# BIT_0.net
KiCad netlist of a schematic drawn in EasyEDA
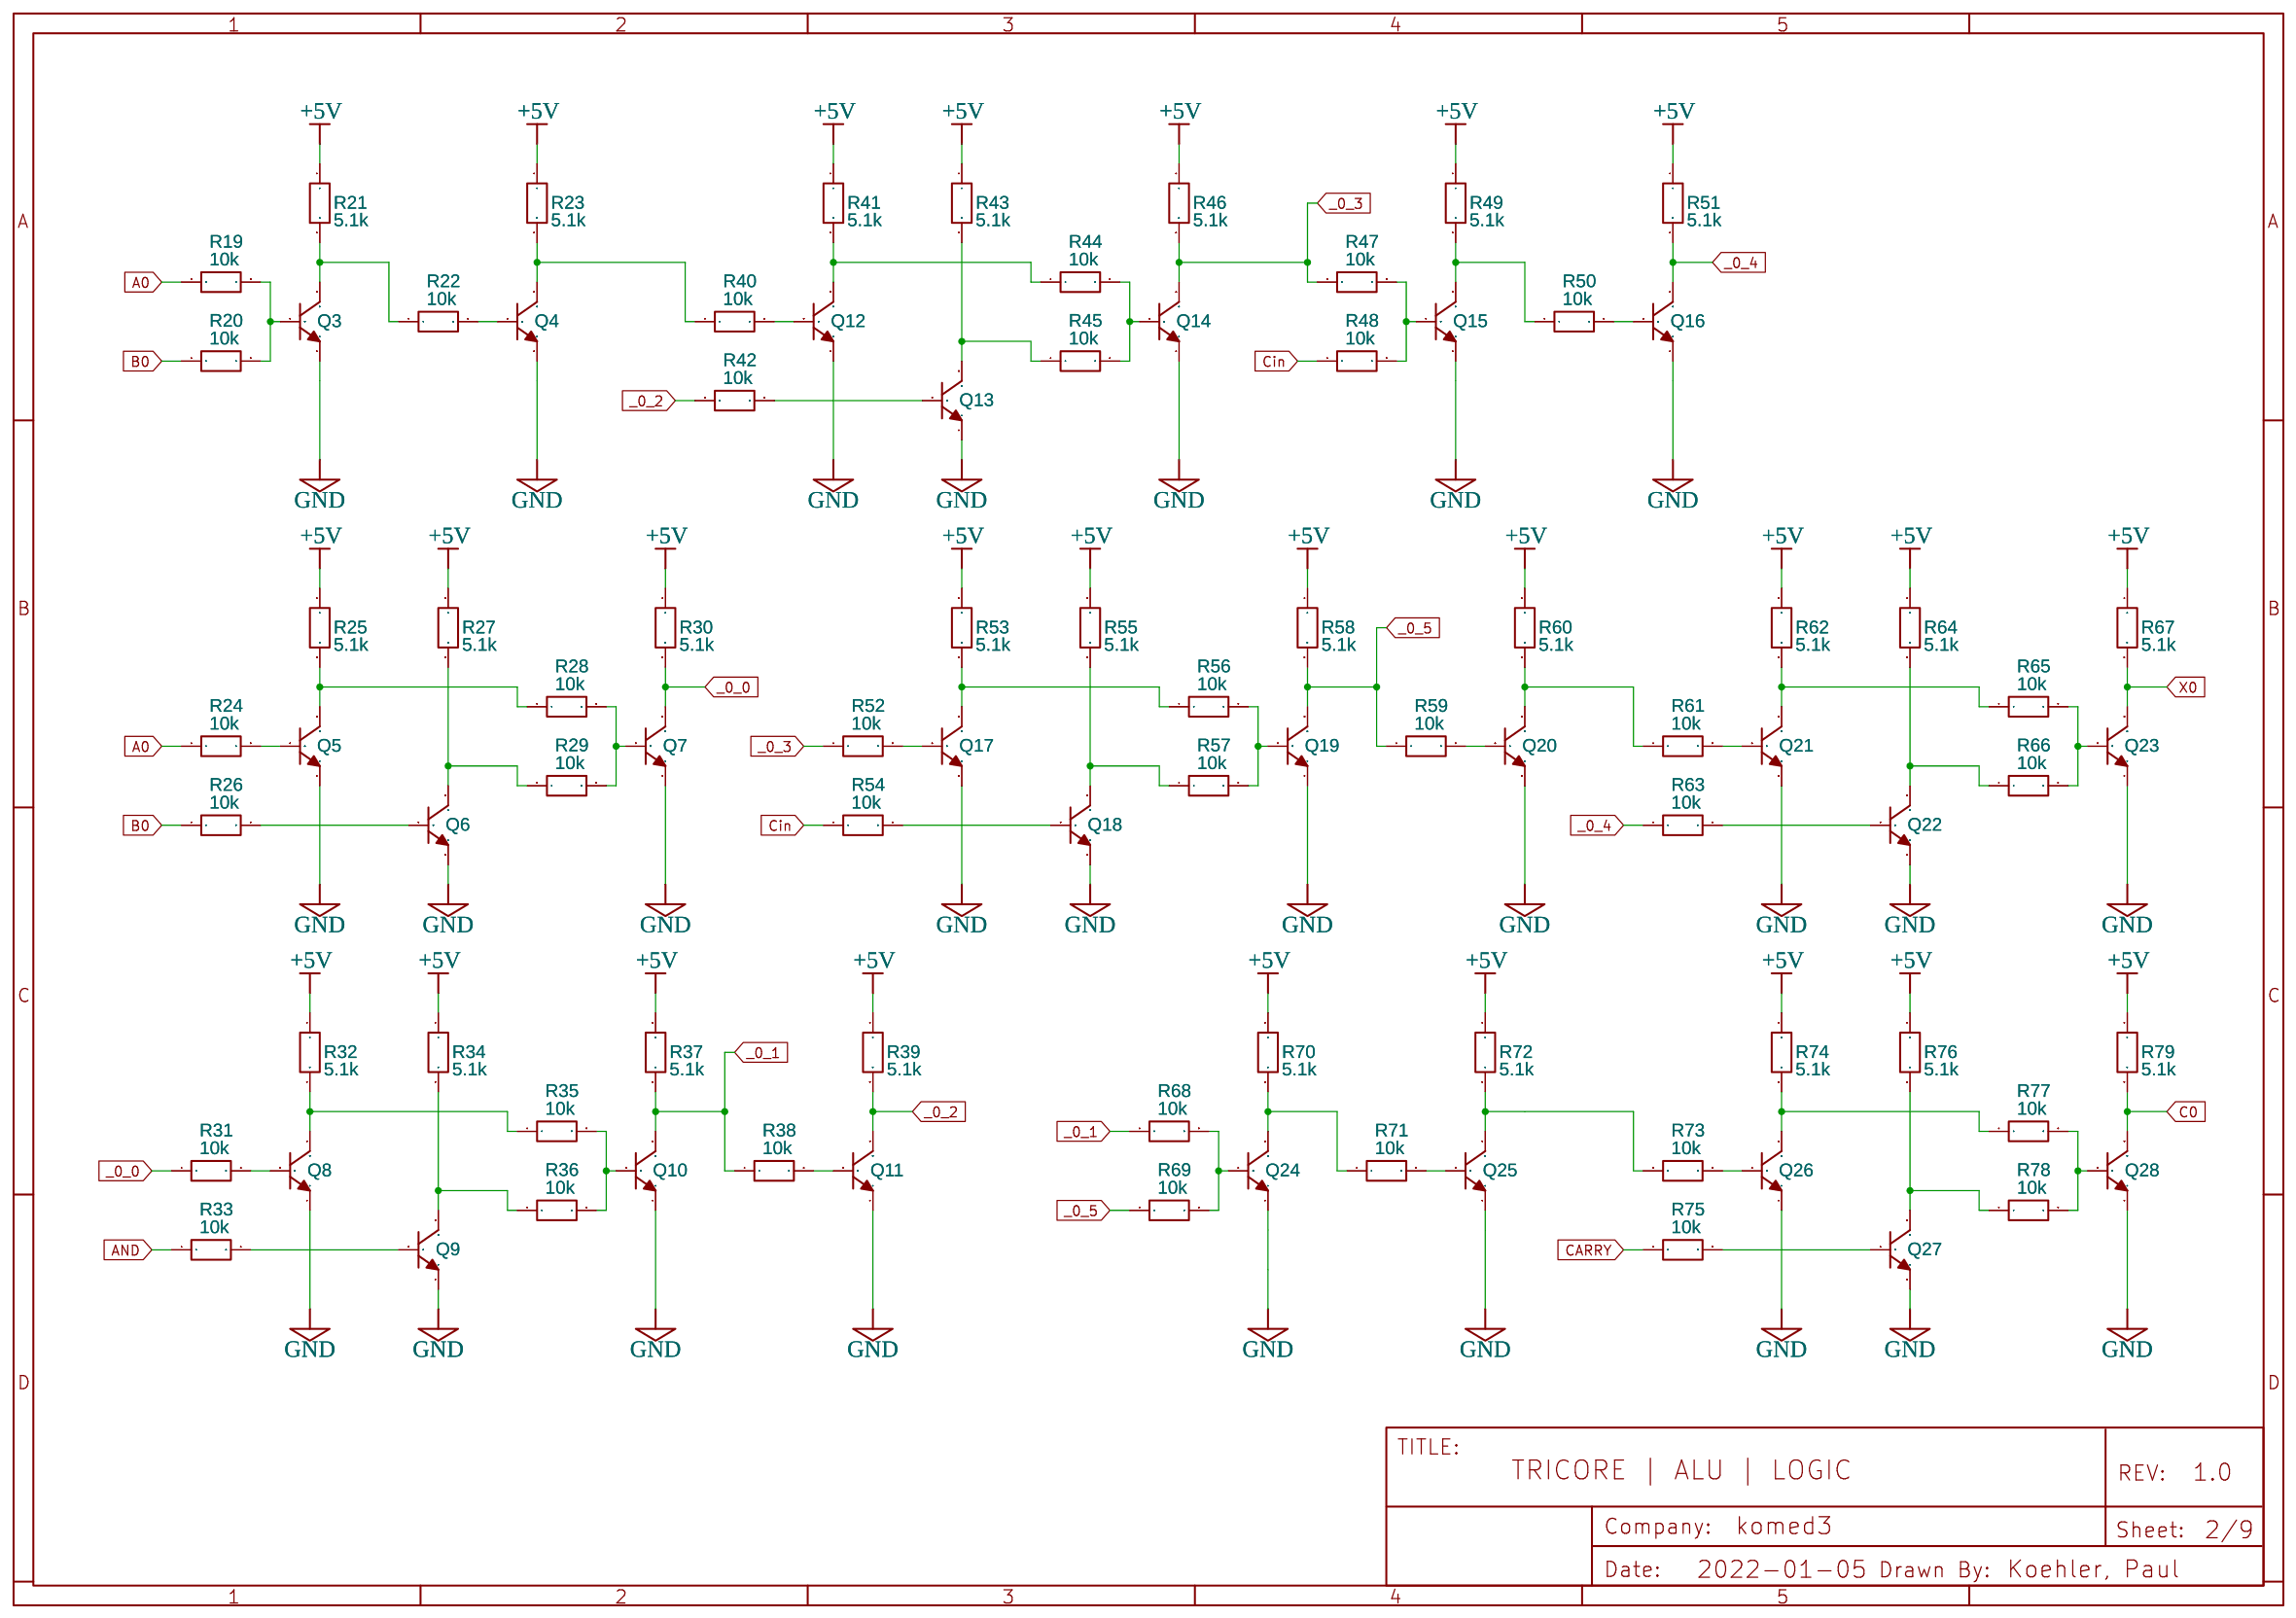
[diagram p0: schematic sheet]

(export (version "E")
  (design (tool "Eeschema 10.0.6"))
  (components
    (comp (ref "Q3")
      (value "2N3904(TO-92)")
      (fields (field (name "BOM_Manufacturer Part") "2N3904") (field (name "BOM_Supplier Part") "C118538"))
      (libsource (lib "") (part "2N3904(TO-92)"))
    )
    (comp (ref "Q4")
      (value "2N3904(TO-92)")
      (fields (field (name "BOM_Manufacturer Part") "2N3904") (field (name "BOM_Supplier Part") "C118538"))
      (libsource (lib "") (part "2N3904(TO-92)"))
    )
    (comp (ref "Q5")
      (value "2N3904(TO-92)")
      (fields (field (name "BOM_Manufacturer Part") "2N3904") (field (name "BOM_Supplier Part") "C118538"))
      (libsource (lib "") (part "2N3904(TO-92)"))
    )
    (comp (ref "Q6")
      (value "2N3904(TO-92)")
      (fields (field (name "BOM_Manufacturer Part") "2N3904") (field (name "BOM_Supplier Part") "C118538"))
      (libsource (lib "") (part "2N3904(TO-92)"))
    )
    (comp (ref "Q7")
      (value "2N3904(TO-92)")
      (fields (field (name "BOM_Manufacturer Part") "2N3904") (field (name "BOM_Supplier Part") "C118538"))
      (libsource (lib "") (part "2N3904(TO-92)"))
    )
    (comp (ref "Q8")
      (value "2N3904(TO-92)")
      (fields (field (name "BOM_Manufacturer Part") "2N3904") (field (name "BOM_Supplier Part") "C118538"))
      (libsource (lib "") (part "2N3904(TO-92)"))
    )
    (comp (ref "Q9")
      (value "2N3904(TO-92)")
      (fields (field (name "BOM_Manufacturer Part") "2N3904") (field (name "BOM_Supplier Part") "C118538"))
      (libsource (lib "") (part "2N3904(TO-92)"))
    )
    (comp (ref "Q10")
      (value "2N3904(TO-92)")
      (fields (field (name "BOM_Manufacturer Part") "2N3904") (field (name "BOM_Supplier Part") "C118538"))
      (libsource (lib "") (part "2N3904(TO-92)"))
    )
    (comp (ref "Q11")
      (value "2N3904(TO-92)")
      (fields (field (name "BOM_Manufacturer Part") "2N3904") (field (name "BOM_Supplier Part") "C118538"))
      (libsource (lib "") (part "2N3904(TO-92)"))
    )
    (comp (ref "Q12")
      (value "2N3904(TO-92)")
      (fields (field (name "BOM_Manufacturer Part") "2N3904") (field (name "BOM_Supplier Part") "C118538"))
      (libsource (lib "") (part "2N3904(TO-92)"))
    )
    (comp (ref "Q13")
      (value "2N3904(TO-92)")
      (fields (field (name "BOM_Manufacturer Part") "2N3904") (field (name "BOM_Supplier Part") "C118538"))
      (libsource (lib "") (part "2N3904(TO-92)"))
    )
    (comp (ref "Q14")
      (value "2N3904(TO-92)")
      (fields (field (name "BOM_Manufacturer Part") "2N3904") (field (name "BOM_Supplier Part") "C118538"))
      (libsource (lib "") (part "2N3904(TO-92)"))
    )
    (comp (ref "Q15")
      (value "2N3904(TO-92)")
      (fields (field (name "BOM_Manufacturer Part") "2N3904") (field (name "BOM_Supplier Part") "C118538"))
      (libsource (lib "") (part "2N3904(TO-92)"))
    )
    (comp (ref "Q16")
      (value "2N3904(TO-92)")
      (fields (field (name "BOM_Manufacturer Part") "2N3904") (field (name "BOM_Supplier Part") "C118538"))
      (libsource (lib "") (part "2N3904(TO-92)"))
    )
    (comp (ref "Q17")
      (value "2N3904(TO-92)")
      (fields (field (name "BOM_Manufacturer Part") "2N3904") (field (name "BOM_Supplier Part") "C118538"))
      (libsource (lib "") (part "2N3904(TO-92)"))
    )
    (comp (ref "Q18")
      (value "2N3904(TO-92)")
      (fields (field (name "BOM_Manufacturer Part") "2N3904") (field (name "BOM_Supplier Part") "C118538"))
      (libsource (lib "") (part "2N3904(TO-92)"))
    )
    (comp (ref "Q19")
      (value "2N3904(TO-92)")
      (fields (field (name "BOM_Manufacturer Part") "2N3904") (field (name "BOM_Supplier Part") "C118538"))
      (libsource (lib "") (part "2N3904(TO-92)"))
    )
    (comp (ref "Q20")
      (value "2N3904(TO-92)")
      (fields (field (name "BOM_Manufacturer Part") "2N3904") (field (name "BOM_Supplier Part") "C118538"))
      (libsource (lib "") (part "2N3904(TO-92)"))
    )
    (comp (ref "Q21")
      (value "2N3904(TO-92)")
      (fields (field (name "BOM_Manufacturer Part") "2N3904") (field (name "BOM_Supplier Part") "C118538"))
      (libsource (lib "") (part "2N3904(TO-92)"))
    )
    (comp (ref "Q22")
      (value "2N3904(TO-92)")
      (fields (field (name "BOM_Manufacturer Part") "2N3904") (field (name "BOM_Supplier Part") "C118538"))
      (libsource (lib "") (part "2N3904(TO-92)"))
    )
    (comp (ref "Q23")
      (value "2N3904(TO-92)")
      (fields (field (name "BOM_Manufacturer Part") "2N3904") (field (name "BOM_Supplier Part") "C118538"))
      (libsource (lib "") (part "2N3904(TO-92)"))
    )
    (comp (ref "Q24")
      (value "2N3904(TO-92)")
      (fields (field (name "BOM_Manufacturer Part") "2N3904") (field (name "BOM_Supplier Part") "C118538"))
      (libsource (lib "") (part "2N3904(TO-92)"))
    )
    (comp (ref "Q25")
      (value "2N3904(TO-92)")
      (fields (field (name "BOM_Manufacturer Part") "2N3904") (field (name "BOM_Supplier Part") "C118538"))
      (libsource (lib "") (part "2N3904(TO-92)"))
    )
    (comp (ref "Q26")
      (value "2N3904(TO-92)")
      (fields (field (name "BOM_Manufacturer Part") "2N3904") (field (name "BOM_Supplier Part") "C118538"))
      (libsource (lib "") (part "2N3904(TO-92)"))
    )
    (comp (ref "Q27")
      (value "2N3904(TO-92)")
      (fields (field (name "BOM_Manufacturer Part") "2N3904") (field (name "BOM_Supplier Part") "C118538"))
      (libsource (lib "") (part "2N3904(TO-92)"))
    )
    (comp (ref "Q28")
      (value "2N3904(TO-92)")
      (fields (field (name "BOM_Manufacturer Part") "2N3904") (field (name "BOM_Supplier Part") "C118538"))
      (libsource (lib "") (part "2N3904(TO-92)"))
    )
    (comp (ref "R19") (value "10k") (libsource (lib "") (part "R_AXIAL-0.3_EU_1")))
    (comp (ref "R20") (value "10k") (libsource (lib "") (part "R_AXIAL-0.3_EU_1")))
    (comp (ref "R21") (value "5.1k") (libsource (lib "") (part "R_AXIAL-0.3_EU")))
    (comp (ref "R22") (value "10k") (libsource (lib "") (part "R_AXIAL-0.3_EU_1")))
    (comp (ref "R23") (value "5.1k") (libsource (lib "") (part "R_AXIAL-0.3_EU")))
    (comp (ref "R24") (value "10k") (libsource (lib "") (part "R_AXIAL-0.3_EU_1")))
    (comp (ref "R25") (value "5.1k") (libsource (lib "") (part "R_AXIAL-0.3_EU")))
    (comp (ref "R26") (value "10k") (libsource (lib "") (part "R_AXIAL-0.3_EU_1")))
    (comp (ref "R27") (value "5.1k") (libsource (lib "") (part "R_AXIAL-0.3_EU")))
    (comp (ref "R28") (value "10k") (libsource (lib "") (part "R_AXIAL-0.3_EU_1")))
    (comp (ref "R29") (value "10k") (libsource (lib "") (part "R_AXIAL-0.3_EU_1")))
    (comp (ref "R30") (value "5.1k") (libsource (lib "") (part "R_AXIAL-0.3_EU")))
    (comp (ref "R31") (value "10k") (libsource (lib "") (part "R_AXIAL-0.3_EU_1")))
    (comp (ref "R32") (value "5.1k") (libsource (lib "") (part "R_AXIAL-0.3_EU")))
    (comp (ref "R33") (value "10k") (libsource (lib "") (part "R_AXIAL-0.3_EU_1")))
    (comp (ref "R34") (value "5.1k") (libsource (lib "") (part "R_AXIAL-0.3_EU")))
    (comp (ref "R35") (value "10k") (libsource (lib "") (part "R_AXIAL-0.3_EU_1")))
    (comp (ref "R36") (value "10k") (libsource (lib "") (part "R_AXIAL-0.3_EU_1")))
    (comp (ref "R37") (value "5.1k") (libsource (lib "") (part "R_AXIAL-0.3_EU")))
    (comp (ref "R38") (value "10k") (libsource (lib "") (part "R_AXIAL-0.3_EU_1")))
    (comp (ref "R39") (value "5.1k") (libsource (lib "") (part "R_AXIAL-0.3_EU")))
    (comp (ref "R40") (value "10k") (libsource (lib "") (part "R_AXIAL-0.3_EU_1")))
    (comp (ref "R41") (value "5.1k") (libsource (lib "") (part "R_AXIAL-0.3_EU")))
    (comp (ref "R42") (value "10k") (libsource (lib "") (part "R_AXIAL-0.3_EU_1")))
    (comp (ref "R43") (value "5.1k") (libsource (lib "") (part "R_AXIAL-0.3_EU")))
    (comp (ref "R44") (value "10k") (libsource (lib "") (part "R_AXIAL-0.3_EU_1")))
    (comp (ref "R45") (value "10k") (libsource (lib "") (part "R_AXIAL-0.3_EU_1")))
    (comp (ref "R46") (value "5.1k") (libsource (lib "") (part "R_AXIAL-0.3_EU")))
    (comp (ref "R47") (value "10k") (libsource (lib "") (part "R_AXIAL-0.3_EU_1")))
    (comp (ref "R48") (value "10k") (libsource (lib "") (part "R_AXIAL-0.3_EU_1")))
    (comp (ref "R49") (value "5.1k") (libsource (lib "") (part "R_AXIAL-0.3_EU")))
    (comp (ref "R50") (value "10k") (libsource (lib "") (part "R_AXIAL-0.3_EU_1")))
    (comp (ref "R51") (value "5.1k") (libsource (lib "") (part "R_AXIAL-0.3_EU")))
    (comp (ref "R52") (value "10k") (libsource (lib "") (part "R_AXIAL-0.3_EU_1")))
    (comp (ref "R53") (value "5.1k") (libsource (lib "") (part "R_AXIAL-0.3_EU")))
    (comp (ref "R54") (value "10k") (libsource (lib "") (part "R_AXIAL-0.3_EU_1")))
    (comp (ref "R55") (value "5.1k") (libsource (lib "") (part "R_AXIAL-0.3_EU")))
    (comp (ref "R56") (value "10k") (libsource (lib "") (part "R_AXIAL-0.3_EU_1")))
    (comp (ref "R57") (value "10k") (libsource (lib "") (part "R_AXIAL-0.3_EU_1")))
    (comp (ref "R58") (value "5.1k") (libsource (lib "") (part "R_AXIAL-0.3_EU")))
    (comp (ref "R59") (value "10k") (libsource (lib "") (part "R_AXIAL-0.3_EU_1")))
    (comp (ref "R60") (value "5.1k") (libsource (lib "") (part "R_AXIAL-0.3_EU")))
    (comp (ref "R61") (value "10k") (libsource (lib "") (part "R_AXIAL-0.3_EU_1")))
    (comp (ref "R62") (value "5.1k") (libsource (lib "") (part "R_AXIAL-0.3_EU")))
    (comp (ref "R63") (value "10k") (libsource (lib "") (part "R_AXIAL-0.3_EU_1")))
    (comp (ref "R64") (value "5.1k") (libsource (lib "") (part "R_AXIAL-0.3_EU")))
    (comp (ref "R65") (value "10k") (libsource (lib "") (part "R_AXIAL-0.3_EU_1")))
    (comp (ref "R66") (value "10k") (libsource (lib "") (part "R_AXIAL-0.3_EU_1")))
    (comp (ref "R67") (value "5.1k") (libsource (lib "") (part "R_AXIAL-0.3_EU")))
    (comp (ref "R68") (value "10k") (libsource (lib "") (part "R_AXIAL-0.3_EU_1")))
    (comp (ref "R69") (value "10k") (libsource (lib "") (part "R_AXIAL-0.3_EU_1")))
    (comp (ref "R70") (value "5.1k") (libsource (lib "") (part "R_AXIAL-0.3_EU")))
    (comp (ref "R71") (value "10k") (libsource (lib "") (part "R_AXIAL-0.3_EU_1")))
    (comp (ref "R72") (value "5.1k") (libsource (lib "") (part "R_AXIAL-0.3_EU")))
    (comp (ref "R73") (value "10k") (libsource (lib "") (part "R_AXIAL-0.3_EU_1")))
    (comp (ref "R74") (value "5.1k") (libsource (lib "") (part "R_AXIAL-0.3_EU")))
    (comp (ref "R75") (value "10k") (libsource (lib "") (part "R_AXIAL-0.3_EU_1")))
    (comp (ref "R76") (value "5.1k") (libsource (lib "") (part "R_AXIAL-0.3_EU")))
    (comp (ref "R77") (value "10k") (libsource (lib "") (part "R_AXIAL-0.3_EU_1")))
    (comp (ref "R78") (value "10k") (libsource (lib "") (part "R_AXIAL-0.3_EU_1")))
    (comp (ref "R79") (value "5.1k") (libsource (lib "") (part "R_AXIAL-0.3_EU")))
  )
  (nets
    (net (code "1") (name "+5V") (class "Default")
      (node (ref "R21") (pin "1") (pinfunction "1_1") (pintype "unspecified"))
      (node (ref "R23") (pin "1") (pinfunction "1_1") (pintype "unspecified"))
      (node (ref "R25") (pin "1") (pinfunction "1_1") (pintype "unspecified"))
      (node (ref "R27") (pin "1") (pinfunction "1_1") (pintype "unspecified"))
      (node (ref "R30") (pin "1") (pinfunction "1_1") (pintype "unspecified"))
      (node (ref "R32") (pin "1") (pinfunction "1_1") (pintype "unspecified"))
      (node (ref "R34") (pin "1") (pinfunction "1_1") (pintype "unspecified"))
      (node (ref "R37") (pin "1") (pinfunction "1_1") (pintype "unspecified"))
      (node (ref "R39") (pin "1") (pinfunction "1_1") (pintype "unspecified"))
      (node (ref "R41") (pin "1") (pinfunction "1_1") (pintype "unspecified"))
      (node (ref "R43") (pin "1") (pinfunction "1_1") (pintype "unspecified"))
      (node (ref "R46") (pin "1") (pinfunction "1_1") (pintype "unspecified"))
      (node (ref "R49") (pin "1") (pinfunction "1_1") (pintype "unspecified"))
      (node (ref "R51") (pin "1") (pinfunction "1_1") (pintype "unspecified"))
      (node (ref "R53") (pin "1") (pinfunction "1_1") (pintype "unspecified"))
      (node (ref "R55") (pin "1") (pinfunction "1_1") (pintype "unspecified"))
      (node (ref "R58") (pin "1") (pinfunction "1_1") (pintype "unspecified"))
      (node (ref "R60") (pin "1") (pinfunction "1_1") (pintype "unspecified"))
      (node (ref "R62") (pin "1") (pinfunction "1_1") (pintype "unspecified"))
      (node (ref "R64") (pin "1") (pinfunction "1_1") (pintype "unspecified"))
      (node (ref "R67") (pin "1") (pinfunction "1_1") (pintype "unspecified"))
      (node (ref "R70") (pin "1") (pinfunction "1_1") (pintype "unspecified"))
      (node (ref "R72") (pin "1") (pinfunction "1_1") (pintype "unspecified"))
      (node (ref "R74") (pin "1") (pinfunction "1_1") (pintype "unspecified"))
      (node (ref "R76") (pin "1") (pinfunction "1_1") (pintype "unspecified"))
      (node (ref "R79") (pin "1") (pinfunction "1_1") (pintype "unspecified"))
    )
    (net (code "2") (name "A0") (class "Default")
      (node (ref "R19") (pin "1") (pinfunction "1_1") (pintype "unspecified"))
      (node (ref "R24") (pin "1") (pinfunction "1_1") (pintype "unspecified"))
    )
    (net (code "3") (name "AND") (class "Default")
      (node (ref "R33") (pin "1") (pinfunction "1_1") (pintype "unspecified"))
    )
    (net (code "4") (name "B0") (class "Default")
      (node (ref "R20") (pin "1") (pinfunction "1_1") (pintype "unspecified"))
      (node (ref "R26") (pin "1") (pinfunction "1_1") (pintype "unspecified"))
    )
    (net (code "5") (name "C0") (class "Default")
      (node (ref "Q28") (pin "3") (pinfunction "C_3") (pintype "unspecified"))
      (node (ref "R79") (pin "2") (pinfunction "2_2") (pintype "unspecified"))
    )
    (net (code "6") (name "CARRY") (class "Default")
      (node (ref "R75") (pin "1") (pinfunction "1_1") (pintype "unspecified"))
    )
    (net (code "7") (name "Cin") (class "Default")
      (node (ref "R48") (pin "1") (pinfunction "1_1") (pintype "unspecified"))
      (node (ref "R54") (pin "1") (pinfunction "1_1") (pintype "unspecified"))
    )
    (net (code "8") (name "GND") (class "Default")
      (node (ref "Q10") (pin "1") (pinfunction "E_1") (pintype "unspecified"))
      (node (ref "Q11") (pin "1") (pinfunction "E_1") (pintype "unspecified"))
      (node (ref "Q12") (pin "1") (pinfunction "E_1") (pintype "unspecified"))
      (node (ref "Q13") (pin "1") (pinfunction "E_1") (pintype "unspecified"))
      (node (ref "Q14") (pin "1") (pinfunction "E_1") (pintype "unspecified"))
      (node (ref "Q15") (pin "1") (pinfunction "E_1") (pintype "unspecified"))
      (node (ref "Q16") (pin "1") (pinfunction "E_1") (pintype "unspecified"))
      (node (ref "Q17") (pin "1") (pinfunction "E_1") (pintype "unspecified"))
      (node (ref "Q18") (pin "1") (pinfunction "E_1") (pintype "unspecified"))
      (node (ref "Q19") (pin "1") (pinfunction "E_1") (pintype "unspecified"))
      (node (ref "Q20") (pin "1") (pinfunction "E_1") (pintype "unspecified"))
      (node (ref "Q21") (pin "1") (pinfunction "E_1") (pintype "unspecified"))
      (node (ref "Q22") (pin "1") (pinfunction "E_1") (pintype "unspecified"))
      (node (ref "Q23") (pin "1") (pinfunction "E_1") (pintype "unspecified"))
      (node (ref "Q24") (pin "1") (pinfunction "E_1") (pintype "unspecified"))
      (node (ref "Q25") (pin "1") (pinfunction "E_1") (pintype "unspecified"))
      (node (ref "Q26") (pin "1") (pinfunction "E_1") (pintype "unspecified"))
      (node (ref "Q27") (pin "1") (pinfunction "E_1") (pintype "unspecified"))
      (node (ref "Q28") (pin "1") (pinfunction "E_1") (pintype "unspecified"))
      (node (ref "Q3") (pin "1") (pinfunction "E_1") (pintype "unspecified"))
      (node (ref "Q4") (pin "1") (pinfunction "E_1") (pintype "unspecified"))
      (node (ref "Q5") (pin "1") (pinfunction "E_1") (pintype "unspecified"))
      (node (ref "Q6") (pin "1") (pinfunction "E_1") (pintype "unspecified"))
      (node (ref "Q7") (pin "1") (pinfunction "E_1") (pintype "unspecified"))
      (node (ref "Q8") (pin "1") (pinfunction "E_1") (pintype "unspecified"))
      (node (ref "Q9") (pin "1") (pinfunction "E_1") (pintype "unspecified"))
    )
    (net (code "9") (name "Net-(Q3-B)") (class "Default")
      (node (ref "Q3") (pin "2") (pinfunction "B_2") (pintype "unspecified"))
      (node (ref "R19") (pin "2") (pinfunction "2_2") (pintype "unspecified"))
      (node (ref "R20") (pin "2") (pinfunction "2_2") (pintype "unspecified"))
    )
    (net (code "10") (name "Net-(Q3-C)") (class "Default")
      (node (ref "Q3") (pin "3") (pinfunction "C_3") (pintype "unspecified"))
      (node (ref "R21") (pin "2") (pinfunction "2_2") (pintype "unspecified"))
      (node (ref "R22") (pin "1") (pinfunction "1_1") (pintype "unspecified"))
    )
    (net (code "11") (name "Net-(Q4-B)") (class "Default")
      (node (ref "Q4") (pin "2") (pinfunction "B_2") (pintype "unspecified"))
      (node (ref "R22") (pin "2") (pinfunction "2_2") (pintype "unspecified"))
    )
    (net (code "12") (name "Net-(Q4-C)") (class "Default")
      (node (ref "Q4") (pin "3") (pinfunction "C_3") (pintype "unspecified"))
      (node (ref "R23") (pin "2") (pinfunction "2_2") (pintype "unspecified"))
      (node (ref "R40") (pin "1") (pinfunction "1_1") (pintype "unspecified"))
    )
    (net (code "13") (name "Net-(Q5-B)") (class "Default")
      (node (ref "Q5") (pin "2") (pinfunction "B_2") (pintype "unspecified"))
      (node (ref "R24") (pin "2") (pinfunction "2_2") (pintype "unspecified"))
    )
    (net (code "14") (name "Net-(Q5-C)") (class "Default")
      (node (ref "Q5") (pin "3") (pinfunction "C_3") (pintype "unspecified"))
      (node (ref "R25") (pin "2") (pinfunction "2_2") (pintype "unspecified"))
      (node (ref "R28") (pin "1") (pinfunction "1_1") (pintype "unspecified"))
    )
    (net (code "15") (name "Net-(Q6-B)") (class "Default")
      (node (ref "Q6") (pin "2") (pinfunction "B_2") (pintype "unspecified"))
      (node (ref "R26") (pin "2") (pinfunction "2_2") (pintype "unspecified"))
    )
    (net (code "16") (name "Net-(Q6-C)") (class "Default")
      (node (ref "Q6") (pin "3") (pinfunction "C_3") (pintype "unspecified"))
      (node (ref "R27") (pin "2") (pinfunction "2_2") (pintype "unspecified"))
      (node (ref "R29") (pin "1") (pinfunction "1_1") (pintype "unspecified"))
    )
    (net (code "17") (name "Net-(Q7-B)") (class "Default")
      (node (ref "Q7") (pin "2") (pinfunction "B_2") (pintype "unspecified"))
      (node (ref "R28") (pin "2") (pinfunction "2_2") (pintype "unspecified"))
      (node (ref "R29") (pin "2") (pinfunction "2_2") (pintype "unspecified"))
    )
    (net (code "18") (name "Net-(Q8-B)") (class "Default")
      (node (ref "Q8") (pin "2") (pinfunction "B_2") (pintype "unspecified"))
      (node (ref "R31") (pin "2") (pinfunction "2_2") (pintype "unspecified"))
    )
    (net (code "19") (name "Net-(Q8-C)") (class "Default")
      (node (ref "Q8") (pin "3") (pinfunction "C_3") (pintype "unspecified"))
      (node (ref "R32") (pin "2") (pinfunction "2_2") (pintype "unspecified"))
      (node (ref "R35") (pin "1") (pinfunction "1_1") (pintype "unspecified"))
    )
    (net (code "20") (name "Net-(Q9-B)") (class "Default")
      (node (ref "Q9") (pin "2") (pinfunction "B_2") (pintype "unspecified"))
      (node (ref "R33") (pin "2") (pinfunction "2_2") (pintype "unspecified"))
    )
    (net (code "21") (name "Net-(Q9-C)") (class "Default")
      (node (ref "Q9") (pin "3") (pinfunction "C_3") (pintype "unspecified"))
      (node (ref "R34") (pin "2") (pinfunction "2_2") (pintype "unspecified"))
      (node (ref "R36") (pin "1") (pinfunction "1_1") (pintype "unspecified"))
    )
    (net (code "22") (name "Net-(Q10-B)") (class "Default")
      (node (ref "Q10") (pin "2") (pinfunction "B_2") (pintype "unspecified"))
      (node (ref "R35") (pin "2") (pinfunction "2_2") (pintype "unspecified"))
      (node (ref "R36") (pin "2") (pinfunction "2_2") (pintype "unspecified"))
    )
    (net (code "23") (name "Net-(Q11-B)") (class "Default")
      (node (ref "Q11") (pin "2") (pinfunction "B_2") (pintype "unspecified"))
      (node (ref "R38") (pin "2") (pinfunction "2_2") (pintype "unspecified"))
    )
    (net (code "24") (name "Net-(Q12-B)") (class "Default")
      (node (ref "Q12") (pin "2") (pinfunction "B_2") (pintype "unspecified"))
      (node (ref "R40") (pin "2") (pinfunction "2_2") (pintype "unspecified"))
    )
    (net (code "25") (name "Net-(Q12-C)") (class "Default")
      (node (ref "Q12") (pin "3") (pinfunction "C_3") (pintype "unspecified"))
      (node (ref "R41") (pin "2") (pinfunction "2_2") (pintype "unspecified"))
      (node (ref "R44") (pin "1") (pinfunction "1_1") (pintype "unspecified"))
    )
    (net (code "26") (name "Net-(Q13-B)") (class "Default")
      (node (ref "Q13") (pin "2") (pinfunction "B_2") (pintype "unspecified"))
      (node (ref "R42") (pin "2") (pinfunction "2_2") (pintype "unspecified"))
    )
    (net (code "27") (name "Net-(Q13-C)") (class "Default")
      (node (ref "Q13") (pin "3") (pinfunction "C_3") (pintype "unspecified"))
      (node (ref "R43") (pin "2") (pinfunction "2_2") (pintype "unspecified"))
      (node (ref "R45") (pin "1") (pinfunction "1_1") (pintype "unspecified"))
    )
    (net (code "28") (name "Net-(Q14-B)") (class "Default")
      (node (ref "Q14") (pin "2") (pinfunction "B_2") (pintype "unspecified"))
      (node (ref "R44") (pin "2") (pinfunction "2_2") (pintype "unspecified"))
      (node (ref "R45") (pin "2") (pinfunction "2_2") (pintype "unspecified"))
    )
    (net (code "29") (name "Net-(Q15-B)") (class "Default")
      (node (ref "Q15") (pin "2") (pinfunction "B_2") (pintype "unspecified"))
      (node (ref "R47") (pin "2") (pinfunction "2_2") (pintype "unspecified"))
      (node (ref "R48") (pin "2") (pinfunction "2_2") (pintype "unspecified"))
    )
    (net (code "30") (name "Net-(Q15-C)") (class "Default")
      (node (ref "Q15") (pin "3") (pinfunction "C_3") (pintype "unspecified"))
      (node (ref "R49") (pin "2") (pinfunction "2_2") (pintype "unspecified"))
      (node (ref "R50") (pin "1") (pinfunction "1_1") (pintype "unspecified"))
    )
    (net (code "31") (name "Net-(Q16-B)") (class "Default")
      (node (ref "Q16") (pin "2") (pinfunction "B_2") (pintype "unspecified"))
      (node (ref "R50") (pin "2") (pinfunction "2_2") (pintype "unspecified"))
    )
    (net (code "32") (name "Net-(Q17-B)") (class "Default")
      (node (ref "Q17") (pin "2") (pinfunction "B_2") (pintype "unspecified"))
      (node (ref "R52") (pin "2") (pinfunction "2_2") (pintype "unspecified"))
    )
    (net (code "33") (name "Net-(Q17-C)") (class "Default")
      (node (ref "Q17") (pin "3") (pinfunction "C_3") (pintype "unspecified"))
      (node (ref "R53") (pin "2") (pinfunction "2_2") (pintype "unspecified"))
      (node (ref "R56") (pin "1") (pinfunction "1_1") (pintype "unspecified"))
    )
    (net (code "34") (name "Net-(Q18-B)") (class "Default")
      (node (ref "Q18") (pin "2") (pinfunction "B_2") (pintype "unspecified"))
      (node (ref "R54") (pin "2") (pinfunction "2_2") (pintype "unspecified"))
    )
    (net (code "35") (name "Net-(Q18-C)") (class "Default")
      (node (ref "Q18") (pin "3") (pinfunction "C_3") (pintype "unspecified"))
      (node (ref "R55") (pin "2") (pinfunction "2_2") (pintype "unspecified"))
      (node (ref "R57") (pin "1") (pinfunction "1_1") (pintype "unspecified"))
    )
    (net (code "36") (name "Net-(Q19-B)") (class "Default")
      (node (ref "Q19") (pin "2") (pinfunction "B_2") (pintype "unspecified"))
      (node (ref "R56") (pin "2") (pinfunction "2_2") (pintype "unspecified"))
      (node (ref "R57") (pin "2") (pinfunction "2_2") (pintype "unspecified"))
    )
    (net (code "37") (name "Net-(Q20-B)") (class "Default")
      (node (ref "Q20") (pin "2") (pinfunction "B_2") (pintype "unspecified"))
      (node (ref "R59") (pin "2") (pinfunction "2_2") (pintype "unspecified"))
    )
    (net (code "38") (name "Net-(Q20-C)") (class "Default")
      (node (ref "Q20") (pin "3") (pinfunction "C_3") (pintype "unspecified"))
      (node (ref "R60") (pin "2") (pinfunction "2_2") (pintype "unspecified"))
      (node (ref "R61") (pin "1") (pinfunction "1_1") (pintype "unspecified"))
    )
    (net (code "39") (name "Net-(Q21-B)") (class "Default")
      (node (ref "Q21") (pin "2") (pinfunction "B_2") (pintype "unspecified"))
      (node (ref "R61") (pin "2") (pinfunction "2_2") (pintype "unspecified"))
    )
    (net (code "40") (name "Net-(Q21-C)") (class "Default")
      (node (ref "Q21") (pin "3") (pinfunction "C_3") (pintype "unspecified"))
      (node (ref "R62") (pin "2") (pinfunction "2_2") (pintype "unspecified"))
      (node (ref "R65") (pin "1") (pinfunction "1_1") (pintype "unspecified"))
    )
    (net (code "41") (name "Net-(Q22-B)") (class "Default")
      (node (ref "Q22") (pin "2") (pinfunction "B_2") (pintype "unspecified"))
      (node (ref "R63") (pin "2") (pinfunction "2_2") (pintype "unspecified"))
    )
    (net (code "42") (name "Net-(Q22-C)") (class "Default")
      (node (ref "Q22") (pin "3") (pinfunction "C_3") (pintype "unspecified"))
      (node (ref "R64") (pin "2") (pinfunction "2_2") (pintype "unspecified"))
      (node (ref "R66") (pin "1") (pinfunction "1_1") (pintype "unspecified"))
    )
    (net (code "43") (name "Net-(Q23-B)") (class "Default")
      (node (ref "Q23") (pin "2") (pinfunction "B_2") (pintype "unspecified"))
      (node (ref "R65") (pin "2") (pinfunction "2_2") (pintype "unspecified"))
      (node (ref "R66") (pin "2") (pinfunction "2_2") (pintype "unspecified"))
    )
    (net (code "44") (name "Net-(Q24-B)") (class "Default")
      (node (ref "Q24") (pin "2") (pinfunction "B_2") (pintype "unspecified"))
      (node (ref "R68") (pin "2") (pinfunction "2_2") (pintype "unspecified"))
      (node (ref "R69") (pin "2") (pinfunction "2_2") (pintype "unspecified"))
    )
    (net (code "45") (name "Net-(Q24-C)") (class "Default")
      (node (ref "Q24") (pin "3") (pinfunction "C_3") (pintype "unspecified"))
      (node (ref "R70") (pin "2") (pinfunction "2_2") (pintype "unspecified"))
      (node (ref "R71") (pin "1") (pinfunction "1_1") (pintype "unspecified"))
    )
    (net (code "46") (name "Net-(Q25-B)") (class "Default")
      (node (ref "Q25") (pin "2") (pinfunction "B_2") (pintype "unspecified"))
      (node (ref "R71") (pin "2") (pinfunction "2_2") (pintype "unspecified"))
    )
    (net (code "47") (name "Net-(Q25-C)") (class "Default")
      (node (ref "Q25") (pin "3") (pinfunction "C_3") (pintype "unspecified"))
      (node (ref "R72") (pin "2") (pinfunction "2_2") (pintype "unspecified"))
      (node (ref "R73") (pin "1") (pinfunction "1_1") (pintype "unspecified"))
    )
    (net (code "48") (name "Net-(Q26-B)") (class "Default")
      (node (ref "Q26") (pin "2") (pinfunction "B_2") (pintype "unspecified"))
      (node (ref "R73") (pin "2") (pinfunction "2_2") (pintype "unspecified"))
    )
    (net (code "49") (name "Net-(Q26-C)") (class "Default")
      (node (ref "Q26") (pin "3") (pinfunction "C_3") (pintype "unspecified"))
      (node (ref "R74") (pin "2") (pinfunction "2_2") (pintype "unspecified"))
      (node (ref "R77") (pin "1") (pinfunction "1_1") (pintype "unspecified"))
    )
    (net (code "50") (name "Net-(Q27-B)") (class "Default")
      (node (ref "Q27") (pin "2") (pinfunction "B_2") (pintype "unspecified"))
      (node (ref "R75") (pin "2") (pinfunction "2_2") (pintype "unspecified"))
    )
    (net (code "51") (name "Net-(Q27-C)") (class "Default")
      (node (ref "Q27") (pin "3") (pinfunction "C_3") (pintype "unspecified"))
      (node (ref "R76") (pin "2") (pinfunction "2_2") (pintype "unspecified"))
      (node (ref "R78") (pin "1") (pinfunction "1_1") (pintype "unspecified"))
    )
    (net (code "52") (name "Net-(Q28-B)") (class "Default")
      (node (ref "Q28") (pin "2") (pinfunction "B_2") (pintype "unspecified"))
      (node (ref "R77") (pin "2") (pinfunction "2_2") (pintype "unspecified"))
      (node (ref "R78") (pin "2") (pinfunction "2_2") (pintype "unspecified"))
    )
    (net (code "53") (name "X0") (class "Default")
      (node (ref "Q23") (pin "3") (pinfunction "C_3") (pintype "unspecified"))
      (node (ref "R67") (pin "2") (pinfunction "2_2") (pintype "unspecified"))
    )
    (net (code "54") (name "_0_0") (class "Default")
      (node (ref "Q7") (pin "3") (pinfunction "C_3") (pintype "unspecified"))
      (node (ref "R30") (pin "2") (pinfunction "2_2") (pintype "unspecified"))
      (node (ref "R31") (pin "1") (pinfunction "1_1") (pintype "unspecified"))
    )
    (net (code "55") (name "_0_1") (class "Default")
      (node (ref "Q10") (pin "3") (pinfunction "C_3") (pintype "unspecified"))
      (node (ref "R37") (pin "2") (pinfunction "2_2") (pintype "unspecified"))
      (node (ref "R38") (pin "1") (pinfunction "1_1") (pintype "unspecified"))
      (node (ref "R68") (pin "1") (pinfunction "1_1") (pintype "unspecified"))
    )
    (net (code "56") (name "_0_2") (class "Default")
      (node (ref "Q11") (pin "3") (pinfunction "C_3") (pintype "unspecified"))
      (node (ref "R39") (pin "2") (pinfunction "2_2") (pintype "unspecified"))
      (node (ref "R42") (pin "1") (pinfunction "1_1") (pintype "unspecified"))
    )
    (net (code "57") (name "_0_3") (class "Default")
      (node (ref "Q14") (pin "3") (pinfunction "C_3") (pintype "unspecified"))
      (node (ref "R46") (pin "2") (pinfunction "2_2") (pintype "unspecified"))
      (node (ref "R47") (pin "1") (pinfunction "1_1") (pintype "unspecified"))
      (node (ref "R52") (pin "1") (pinfunction "1_1") (pintype "unspecified"))
    )
    (net (code "58") (name "_0_4") (class "Default")
      (node (ref "Q16") (pin "3") (pinfunction "C_3") (pintype "unspecified"))
      (node (ref "R51") (pin "2") (pinfunction "2_2") (pintype "unspecified"))
      (node (ref "R63") (pin "1") (pinfunction "1_1") (pintype "unspecified"))
    )
    (net (code "59") (name "_0_5") (class "Default")
      (node (ref "Q19") (pin "3") (pinfunction "C_3") (pintype "unspecified"))
      (node (ref "R58") (pin "2") (pinfunction "2_2") (pintype "unspecified"))
      (node (ref "R59") (pin "1") (pinfunction "1_1") (pintype "unspecified"))
      (node (ref "R69") (pin "1") (pinfunction "1_1") (pintype "unspecified"))
    )
  )
)
